# Hub.net
KiCad netlist of a schematic drawn in EAGLE
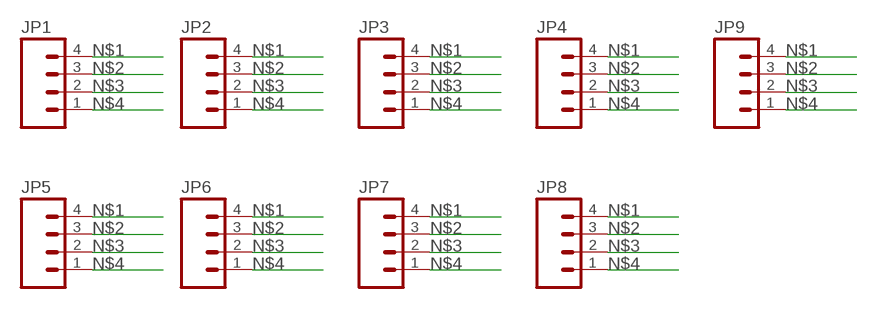
[diagram p0: schematic, sheet 1]

(export (version "E")
  (design (tool "Eeschema 10.0.6"))
  (components
    (comp (ref "JP1")
      (value "M041X04_NO_SILK")
      (footprint "eagle-import:1X04_NO_SILK")
      (libsource (lib "eagle-import") (part "M041X04_NO_SILK"))
    )
    (comp (ref "JP2")
      (value "M041X04_NO_SILK")
      (footprint "eagle-import:1X04_NO_SILK")
      (libsource (lib "eagle-import") (part "M041X04_NO_SILK"))
    )
    (comp (ref "JP3")
      (value "M041X04_NO_SILK")
      (footprint "eagle-import:1X04_NO_SILK")
      (libsource (lib "eagle-import") (part "M041X04_NO_SILK"))
    )
    (comp (ref "JP4")
      (value "M041X04_NO_SILK")
      (footprint "eagle-import:1X04_NO_SILK")
      (libsource (lib "eagle-import") (part "M041X04_NO_SILK"))
    )
    (comp (ref "JP5")
      (value "M041X04_NO_SILK")
      (footprint "eagle-import:1X04_NO_SILK")
      (libsource (lib "eagle-import") (part "M041X04_NO_SILK"))
    )
    (comp (ref "JP6")
      (value "M041X04_NO_SILK")
      (footprint "eagle-import:1X04_NO_SILK")
      (libsource (lib "eagle-import") (part "M041X04_NO_SILK"))
    )
    (comp (ref "JP7")
      (value "M041X04_NO_SILK")
      (footprint "eagle-import:1X04_NO_SILK")
      (libsource (lib "eagle-import") (part "M041X04_NO_SILK"))
    )
    (comp (ref "JP8")
      (value "M041X04_NO_SILK")
      (footprint "eagle-import:1X04_NO_SILK")
      (libsource (lib "eagle-import") (part "M041X04_NO_SILK"))
    )
    (comp (ref "JP9")
      (value "M041X04_NO_SILK")
      (footprint "eagle-import:1X04_NO_SILK")
      (libsource (lib "eagle-import") (part "M041X04_NO_SILK"))
    )
  )
  (nets
    (net (code "1") (name "/N$1") (class "Default")
      (node (ref "JP1") (pin "4") (pinfunction "4_4") (pintype "passive"))
      (node (ref "JP2") (pin "4") (pinfunction "4_4") (pintype "passive"))
      (node (ref "JP3") (pin "4") (pinfunction "4_4") (pintype "passive"))
      (node (ref "JP4") (pin "4") (pinfunction "4_4") (pintype "passive"))
      (node (ref "JP5") (pin "4") (pinfunction "4_4") (pintype "passive"))
      (node (ref "JP6") (pin "4") (pinfunction "4_4") (pintype "passive"))
      (node (ref "JP7") (pin "4") (pinfunction "4_4") (pintype "passive"))
      (node (ref "JP8") (pin "4") (pinfunction "4_4") (pintype "passive"))
      (node (ref "JP9") (pin "4") (pinfunction "4_4") (pintype "passive"))
    )
    (net (code "2") (name "/N$2") (class "Default")
      (node (ref "JP1") (pin "3") (pinfunction "3_3") (pintype "passive"))
      (node (ref "JP2") (pin "3") (pinfunction "3_3") (pintype "passive"))
      (node (ref "JP3") (pin "3") (pinfunction "3_3") (pintype "passive"))
      (node (ref "JP4") (pin "3") (pinfunction "3_3") (pintype "passive"))
      (node (ref "JP5") (pin "3") (pinfunction "3_3") (pintype "passive"))
      (node (ref "JP6") (pin "3") (pinfunction "3_3") (pintype "passive"))
      (node (ref "JP7") (pin "3") (pinfunction "3_3") (pintype "passive"))
      (node (ref "JP8") (pin "3") (pinfunction "3_3") (pintype "passive"))
      (node (ref "JP9") (pin "3") (pinfunction "3_3") (pintype "passive"))
    )
    (net (code "3") (name "/N$3") (class "Default")
      (node (ref "JP1") (pin "2") (pinfunction "2_2") (pintype "passive"))
      (node (ref "JP2") (pin "2") (pinfunction "2_2") (pintype "passive"))
      (node (ref "JP3") (pin "2") (pinfunction "2_2") (pintype "passive"))
      (node (ref "JP4") (pin "2") (pinfunction "2_2") (pintype "passive"))
      (node (ref "JP5") (pin "2") (pinfunction "2_2") (pintype "passive"))
      (node (ref "JP6") (pin "2") (pinfunction "2_2") (pintype "passive"))
      (node (ref "JP7") (pin "2") (pinfunction "2_2") (pintype "passive"))
      (node (ref "JP8") (pin "2") (pinfunction "2_2") (pintype "passive"))
      (node (ref "JP9") (pin "2") (pinfunction "2_2") (pintype "passive"))
    )
    (net (code "4") (name "/N$4") (class "Default")
      (node (ref "JP1") (pin "1") (pinfunction "1_1") (pintype "passive"))
      (node (ref "JP2") (pin "1") (pinfunction "1_1") (pintype "passive"))
      (node (ref "JP3") (pin "1") (pinfunction "1_1") (pintype "passive"))
      (node (ref "JP4") (pin "1") (pinfunction "1_1") (pintype "passive"))
      (node (ref "JP5") (pin "1") (pinfunction "1_1") (pintype "passive"))
      (node (ref "JP6") (pin "1") (pinfunction "1_1") (pintype "passive"))
      (node (ref "JP7") (pin "1") (pinfunction "1_1") (pintype "passive"))
      (node (ref "JP8") (pin "1") (pinfunction "1_1") (pintype "passive"))
      (node (ref "JP9") (pin "1") (pinfunction "1_1") (pintype "passive"))
    )
  )
)
